# carrier_breakout_box_make-before-break.net
KiCad netlist of a schematic drawn in EAGLE
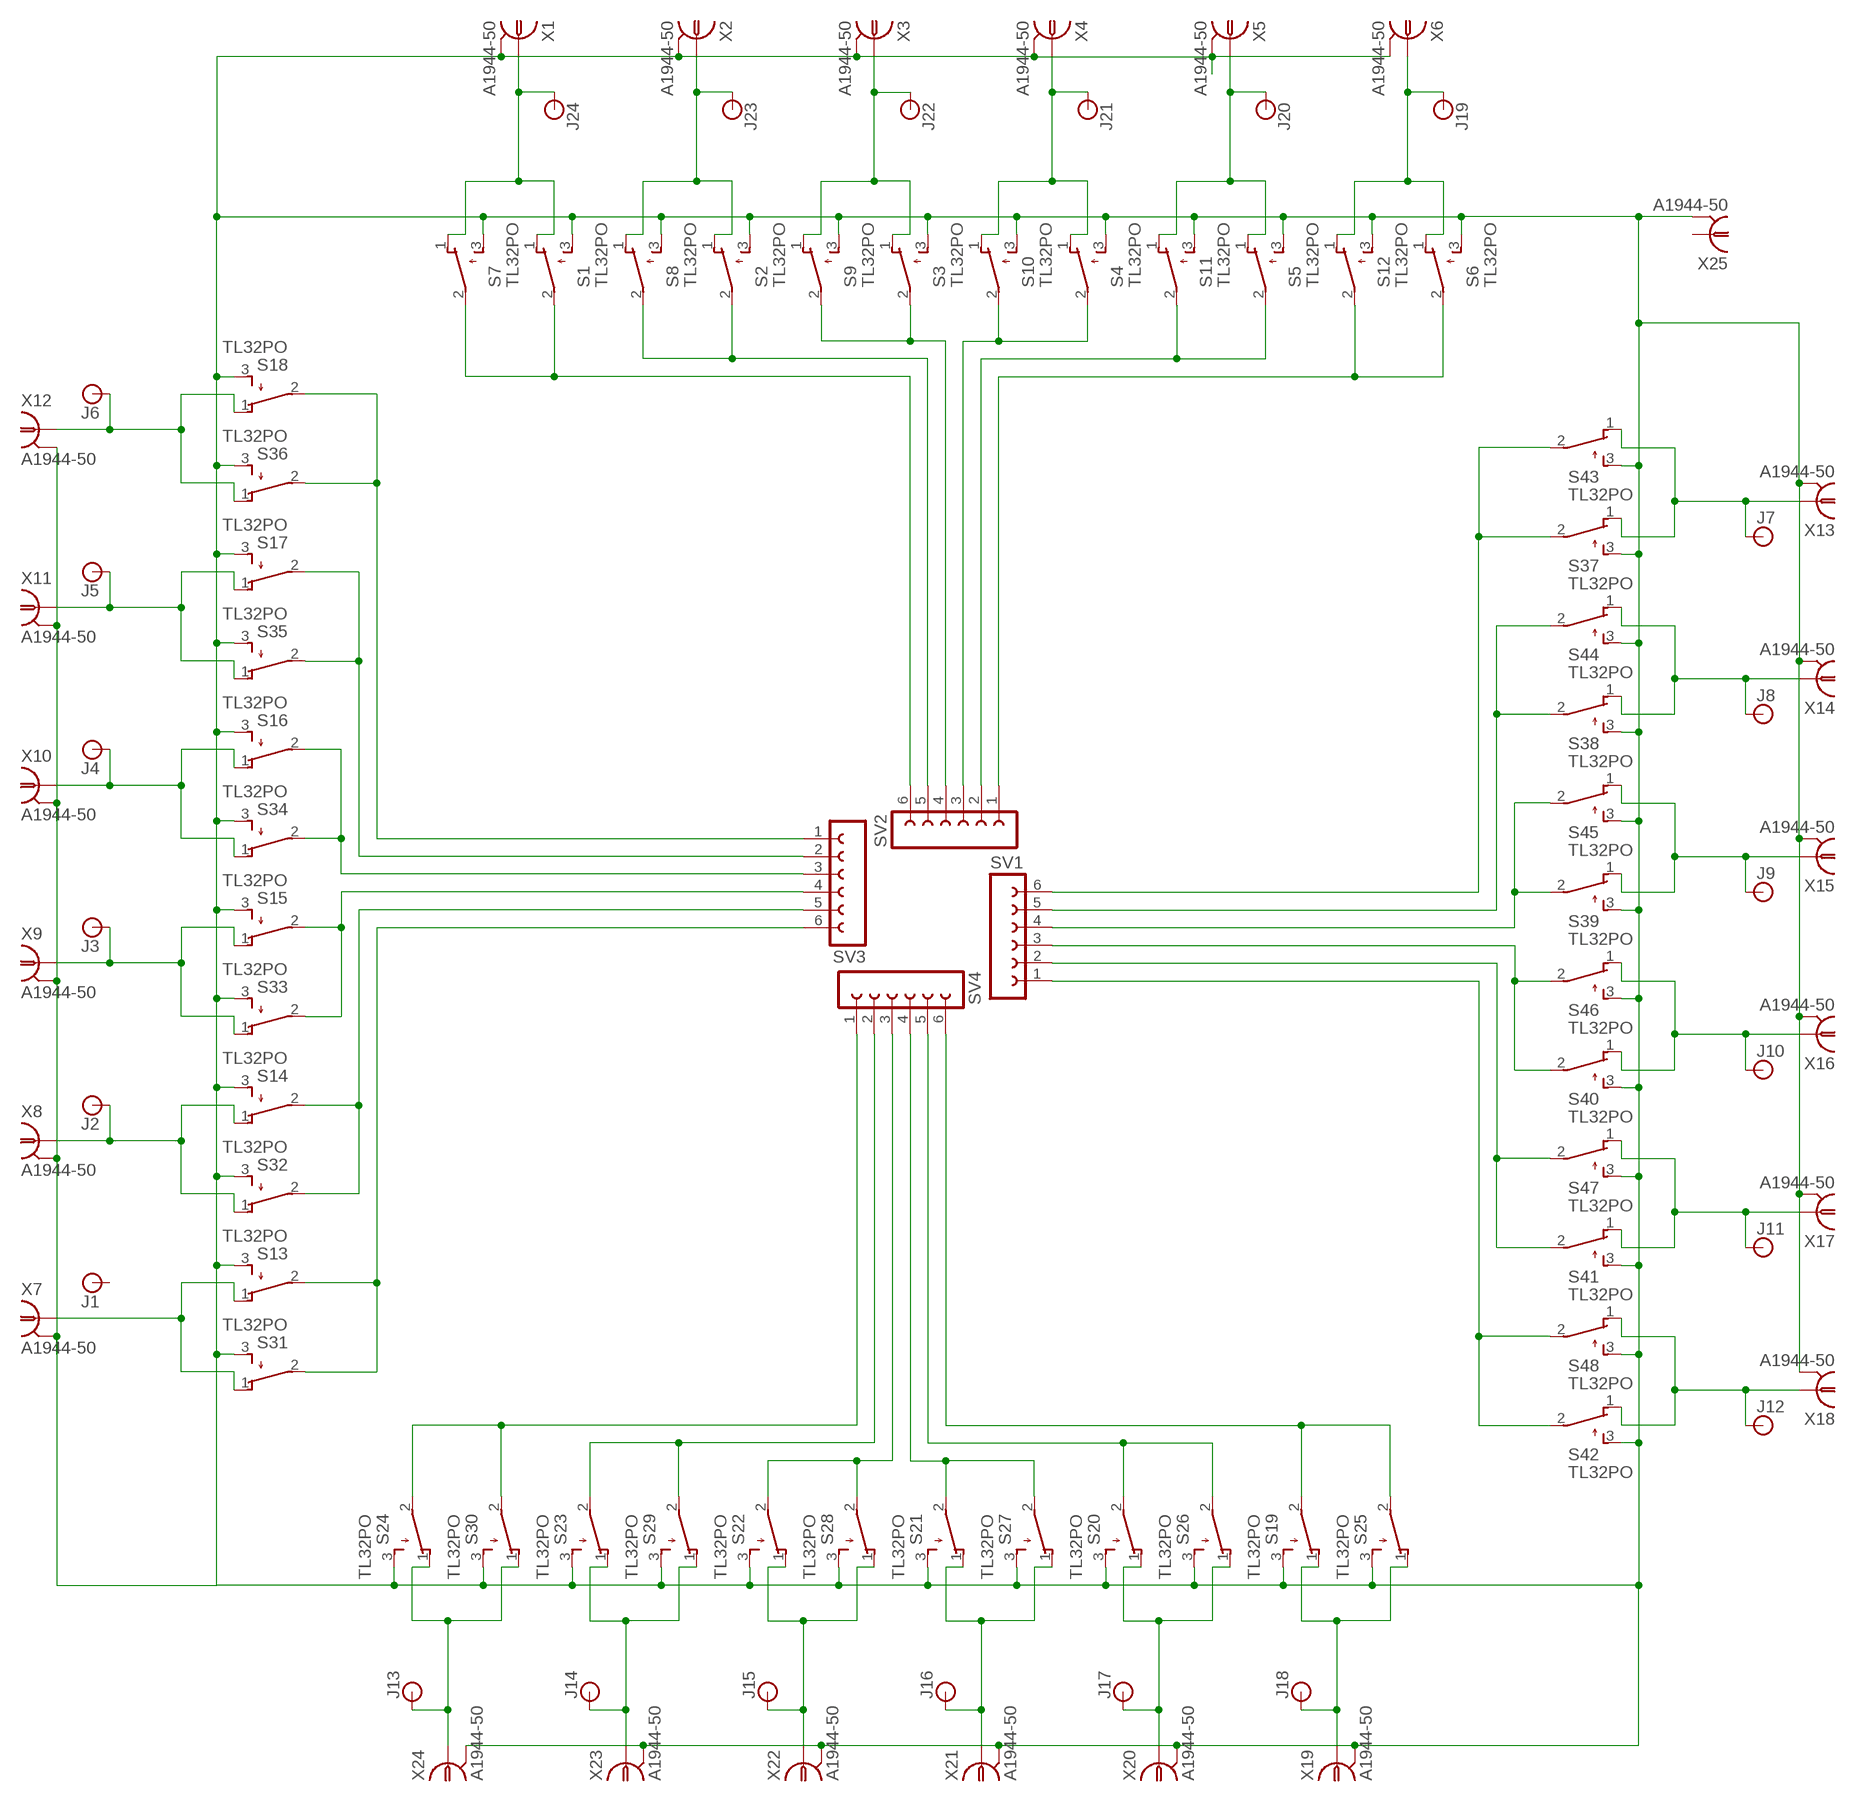
[diagram p0: schematic, sheet 1]

(export (version "E")
  (design (tool "Eeschema 10.0.6"))
  (components
    (comp (ref "J1")
      (value "BANANA_CONN")
      (footprint "eagle-import:BANANA_CONN")
      (libsource (lib "eagle-import") (part "BANANA_CONN"))
    )
    (comp (ref "J2")
      (value "BANANA_CONN")
      (footprint "eagle-import:BANANA_CONN")
      (libsource (lib "eagle-import") (part "BANANA_CONN"))
    )
    (comp (ref "J3")
      (value "BANANA_CONN")
      (footprint "eagle-import:BANANA_CONN")
      (libsource (lib "eagle-import") (part "BANANA_CONN"))
    )
    (comp (ref "J4")
      (value "BANANA_CONN")
      (footprint "eagle-import:BANANA_CONN")
      (libsource (lib "eagle-import") (part "BANANA_CONN"))
    )
    (comp (ref "J5")
      (value "BANANA_CONN")
      (footprint "eagle-import:BANANA_CONN")
      (libsource (lib "eagle-import") (part "BANANA_CONN"))
    )
    (comp (ref "J6")
      (value "BANANA_CONN")
      (footprint "eagle-import:BANANA_CONN")
      (libsource (lib "eagle-import") (part "BANANA_CONN"))
    )
    (comp (ref "J7")
      (value "BANANA_CONN")
      (footprint "eagle-import:BANANA_CONN")
      (libsource (lib "eagle-import") (part "BANANA_CONN"))
    )
    (comp (ref "J8")
      (value "BANANA_CONN")
      (footprint "eagle-import:BANANA_CONN")
      (libsource (lib "eagle-import") (part "BANANA_CONN"))
    )
    (comp (ref "J9")
      (value "BANANA_CONN")
      (footprint "eagle-import:BANANA_CONN")
      (libsource (lib "eagle-import") (part "BANANA_CONN"))
    )
    (comp (ref "J10")
      (value "BANANA_CONN")
      (footprint "eagle-import:BANANA_CONN")
      (libsource (lib "eagle-import") (part "BANANA_CONN"))
    )
    (comp (ref "J11")
      (value "BANANA_CONN")
      (footprint "eagle-import:BANANA_CONN")
      (libsource (lib "eagle-import") (part "BANANA_CONN"))
    )
    (comp (ref "J12")
      (value "BANANA_CONN")
      (footprint "eagle-import:BANANA_CONN")
      (libsource (lib "eagle-import") (part "BANANA_CONN"))
    )
    (comp (ref "J13")
      (value "BANANA_CONN")
      (footprint "eagle-import:BANANA_CONN")
      (libsource (lib "eagle-import") (part "BANANA_CONN"))
    )
    (comp (ref "J14")
      (value "BANANA_CONN")
      (footprint "eagle-import:BANANA_CONN")
      (libsource (lib "eagle-import") (part "BANANA_CONN"))
    )
    (comp (ref "J15")
      (value "BANANA_CONN")
      (footprint "eagle-import:BANANA_CONN")
      (libsource (lib "eagle-import") (part "BANANA_CONN"))
    )
    (comp (ref "J16")
      (value "BANANA_CONN")
      (footprint "eagle-import:BANANA_CONN")
      (libsource (lib "eagle-import") (part "BANANA_CONN"))
    )
    (comp (ref "J17")
      (value "BANANA_CONN")
      (footprint "eagle-import:BANANA_CONN")
      (libsource (lib "eagle-import") (part "BANANA_CONN"))
    )
    (comp (ref "J18")
      (value "BANANA_CONN")
      (footprint "eagle-import:BANANA_CONN")
      (libsource (lib "eagle-import") (part "BANANA_CONN"))
    )
    (comp (ref "J19")
      (value "BANANA_CONN")
      (footprint "eagle-import:BANANA_CONN")
      (libsource (lib "eagle-import") (part "BANANA_CONN"))
    )
    (comp (ref "J20")
      (value "BANANA_CONN")
      (footprint "eagle-import:BANANA_CONN")
      (libsource (lib "eagle-import") (part "BANANA_CONN"))
    )
    (comp (ref "J21")
      (value "BANANA_CONN")
      (footprint "eagle-import:BANANA_CONN")
      (libsource (lib "eagle-import") (part "BANANA_CONN"))
    )
    (comp (ref "J22")
      (value "BANANA_CONN")
      (footprint "eagle-import:BANANA_CONN")
      (libsource (lib "eagle-import") (part "BANANA_CONN"))
    )
    (comp (ref "J23")
      (value "BANANA_CONN")
      (footprint "eagle-import:BANANA_CONN")
      (libsource (lib "eagle-import") (part "BANANA_CONN"))
    )
    (comp (ref "J24")
      (value "BANANA_CONN")
      (footprint "eagle-import:BANANA_CONN")
      (libsource (lib "eagle-import") (part "BANANA_CONN"))
    )
    (comp (ref "S1")
      (value "TL32PO")
      (footprint "eagle-import:TL3XPO")
      (libsource (lib "eagle-import") (part "TL32PO"))
    )
    (comp (ref "S2")
      (value "TL32PO")
      (footprint "eagle-import:TL3XPO")
      (libsource (lib "eagle-import") (part "TL32PO"))
    )
    (comp (ref "S3")
      (value "TL32PO")
      (footprint "eagle-import:TL3XPO")
      (libsource (lib "eagle-import") (part "TL32PO"))
    )
    (comp (ref "S4")
      (value "TL32PO")
      (footprint "eagle-import:TL3XPO")
      (libsource (lib "eagle-import") (part "TL32PO"))
    )
    (comp (ref "S5")
      (value "TL32PO")
      (footprint "eagle-import:TL3XPO")
      (libsource (lib "eagle-import") (part "TL32PO"))
    )
    (comp (ref "S6")
      (value "TL32PO")
      (footprint "eagle-import:TL3XPO")
      (libsource (lib "eagle-import") (part "TL32PO"))
    )
    (comp (ref "S7")
      (value "TL32PO")
      (footprint "eagle-import:TL3XPO")
      (libsource (lib "eagle-import") (part "TL32PO"))
    )
    (comp (ref "S8")
      (value "TL32PO")
      (footprint "eagle-import:TL3XPO")
      (libsource (lib "eagle-import") (part "TL32PO"))
    )
    (comp (ref "S9")
      (value "TL32PO")
      (footprint "eagle-import:TL3XPO")
      (libsource (lib "eagle-import") (part "TL32PO"))
    )
    (comp (ref "S10")
      (value "TL32PO")
      (footprint "eagle-import:TL3XPO")
      (libsource (lib "eagle-import") (part "TL32PO"))
    )
    (comp (ref "S11")
      (value "TL32PO")
      (footprint "eagle-import:TL3XPO")
      (libsource (lib "eagle-import") (part "TL32PO"))
    )
    (comp (ref "S12")
      (value "TL32PO")
      (footprint "eagle-import:TL3XPO")
      (libsource (lib "eagle-import") (part "TL32PO"))
    )
    (comp (ref "S13")
      (value "TL32PO")
      (footprint "eagle-import:TL3XPO")
      (libsource (lib "eagle-import") (part "TL32PO"))
    )
    (comp (ref "S14")
      (value "TL32PO")
      (footprint "eagle-import:TL3XPO")
      (libsource (lib "eagle-import") (part "TL32PO"))
    )
    (comp (ref "S15")
      (value "TL32PO")
      (footprint "eagle-import:TL3XPO")
      (libsource (lib "eagle-import") (part "TL32PO"))
    )
    (comp (ref "S16")
      (value "TL32PO")
      (footprint "eagle-import:TL3XPO")
      (libsource (lib "eagle-import") (part "TL32PO"))
    )
    (comp (ref "S17")
      (value "TL32PO")
      (footprint "eagle-import:TL3XPO")
      (libsource (lib "eagle-import") (part "TL32PO"))
    )
    (comp (ref "S18")
      (value "TL32PO")
      (footprint "eagle-import:TL3XPO")
      (libsource (lib "eagle-import") (part "TL32PO"))
    )
    (comp (ref "S19")
      (value "TL32PO")
      (footprint "eagle-import:TL3XPO")
      (libsource (lib "eagle-import") (part "TL32PO"))
    )
    (comp (ref "S20")
      (value "TL32PO")
      (footprint "eagle-import:TL3XPO")
      (libsource (lib "eagle-import") (part "TL32PO"))
    )
    (comp (ref "S21")
      (value "TL32PO")
      (footprint "eagle-import:TL3XPO")
      (libsource (lib "eagle-import") (part "TL32PO"))
    )
    (comp (ref "S22")
      (value "TL32PO")
      (footprint "eagle-import:TL3XPO")
      (libsource (lib "eagle-import") (part "TL32PO"))
    )
    (comp (ref "S23")
      (value "TL32PO")
      (footprint "eagle-import:TL3XPO")
      (libsource (lib "eagle-import") (part "TL32PO"))
    )
    (comp (ref "S24")
      (value "TL32PO")
      (footprint "eagle-import:TL3XPO")
      (libsource (lib "eagle-import") (part "TL32PO"))
    )
    (comp (ref "S25")
      (value "TL32PO")
      (footprint "eagle-import:TL3XPO")
      (libsource (lib "eagle-import") (part "TL32PO"))
    )
    (comp (ref "S26")
      (value "TL32PO")
      (footprint "eagle-import:TL3XPO")
      (libsource (lib "eagle-import") (part "TL32PO"))
    )
    (comp (ref "S27")
      (value "TL32PO")
      (footprint "eagle-import:TL3XPO")
      (libsource (lib "eagle-import") (part "TL32PO"))
    )
    (comp (ref "S28")
      (value "TL32PO")
      (footprint "eagle-import:TL3XPO")
      (libsource (lib "eagle-import") (part "TL32PO"))
    )
    (comp (ref "S29")
      (value "TL32PO")
      (footprint "eagle-import:TL3XPO")
      (libsource (lib "eagle-import") (part "TL32PO"))
    )
    (comp (ref "S30")
      (value "TL32PO")
      (footprint "eagle-import:TL3XPO")
      (libsource (lib "eagle-import") (part "TL32PO"))
    )
    (comp (ref "S31")
      (value "TL32PO")
      (footprint "eagle-import:TL3XPO")
      (libsource (lib "eagle-import") (part "TL32PO"))
    )
    (comp (ref "S32")
      (value "TL32PO")
      (footprint "eagle-import:TL3XPO")
      (libsource (lib "eagle-import") (part "TL32PO"))
    )
    (comp (ref "S33")
      (value "TL32PO")
      (footprint "eagle-import:TL3XPO")
      (libsource (lib "eagle-import") (part "TL32PO"))
    )
    (comp (ref "S34")
      (value "TL32PO")
      (footprint "eagle-import:TL3XPO")
      (libsource (lib "eagle-import") (part "TL32PO"))
    )
    (comp (ref "S35")
      (value "TL32PO")
      (footprint "eagle-import:TL3XPO")
      (libsource (lib "eagle-import") (part "TL32PO"))
    )
    (comp (ref "S36")
      (value "TL32PO")
      (footprint "eagle-import:TL3XPO")
      (libsource (lib "eagle-import") (part "TL32PO"))
    )
    (comp (ref "S37")
      (value "TL32PO")
      (footprint "eagle-import:TL3XPO")
      (libsource (lib "eagle-import") (part "TL32PO"))
    )
    (comp (ref "S38")
      (value "TL32PO")
      (footprint "eagle-import:TL3XPO")
      (libsource (lib "eagle-import") (part "TL32PO"))
    )
    (comp (ref "S39")
      (value "TL32PO")
      (footprint "eagle-import:TL3XPO")
      (libsource (lib "eagle-import") (part "TL32PO"))
    )
    (comp (ref "S40")
      (value "TL32PO")
      (footprint "eagle-import:TL3XPO")
      (libsource (lib "eagle-import") (part "TL32PO"))
    )
    (comp (ref "S41")
      (value "TL32PO")
      (footprint "eagle-import:TL3XPO")
      (libsource (lib "eagle-import") (part "TL32PO"))
    )
    (comp (ref "S42")
      (value "TL32PO")
      (footprint "eagle-import:TL3XPO")
      (libsource (lib "eagle-import") (part "TL32PO"))
    )
    (comp (ref "S43")
      (value "TL32PO")
      (footprint "eagle-import:TL3XPO")
      (libsource (lib "eagle-import") (part "TL32PO"))
    )
    (comp (ref "S44")
      (value "TL32PO")
      (footprint "eagle-import:TL3XPO")
      (libsource (lib "eagle-import") (part "TL32PO"))
    )
    (comp (ref "S45")
      (value "TL32PO")
      (footprint "eagle-import:TL3XPO")
      (libsource (lib "eagle-import") (part "TL32PO"))
    )
    (comp (ref "S46")
      (value "TL32PO")
      (footprint "eagle-import:TL3XPO")
      (libsource (lib "eagle-import") (part "TL32PO"))
    )
    (comp (ref "S47")
      (value "TL32PO")
      (footprint "eagle-import:TL3XPO")
      (libsource (lib "eagle-import") (part "TL32PO"))
    )
    (comp (ref "S48")
      (value "TL32PO")
      (footprint "eagle-import:TL3XPO")
      (libsource (lib "eagle-import") (part "TL32PO"))
    )
    (comp (ref "SV1")
      (value "FE06-1")
      (footprint "eagle-import:FE06")
      (libsource (lib "eagle-import") (part "FE06-1"))
    )
    (comp (ref "SV2")
      (value "FE06-1")
      (footprint "eagle-import:FE06")
      (libsource (lib "eagle-import") (part "FE06-1"))
    )
    (comp (ref "SV3")
      (value "FE06-1")
      (footprint "eagle-import:FE06")
      (libsource (lib "eagle-import") (part "FE06-1"))
    )
    (comp (ref "SV4")
      (value "FE06-1")
      (footprint "eagle-import:FE06")
      (libsource (lib "eagle-import") (part "FE06-1"))
    )
    (comp (ref "X1")
      (value "A1944-50")
      (footprint "eagle-import:A1944")
      (libsource (lib "eagle-import") (part "A1944-50"))
    )
    (comp (ref "X2")
      (value "A1944-50")
      (footprint "eagle-import:A1944")
      (libsource (lib "eagle-import") (part "A1944-50"))
    )
    (comp (ref "X3")
      (value "A1944-50")
      (footprint "eagle-import:A1944")
      (libsource (lib "eagle-import") (part "A1944-50"))
    )
    (comp (ref "X4")
      (value "A1944-50")
      (footprint "eagle-import:A1944")
      (libsource (lib "eagle-import") (part "A1944-50"))
    )
    (comp (ref "X5")
      (value "A1944-50")
      (footprint "eagle-import:A1944")
      (libsource (lib "eagle-import") (part "A1944-50"))
    )
    (comp (ref "X6")
      (value "A1944-50")
      (footprint "eagle-import:A1944")
      (libsource (lib "eagle-import") (part "A1944-50"))
    )
    (comp (ref "X7")
      (value "A1944-50")
      (footprint "eagle-import:A1944")
      (libsource (lib "eagle-import") (part "A1944-50"))
    )
    (comp (ref "X8")
      (value "A1944-50")
      (footprint "eagle-import:A1944")
      (libsource (lib "eagle-import") (part "A1944-50"))
    )
    (comp (ref "X9")
      (value "A1944-50")
      (footprint "eagle-import:A1944")
      (libsource (lib "eagle-import") (part "A1944-50"))
    )
    (comp (ref "X10")
      (value "A1944-50")
      (footprint "eagle-import:A1944")
      (libsource (lib "eagle-import") (part "A1944-50"))
    )
    (comp (ref "X11")
      (value "A1944-50")
      (footprint "eagle-import:A1944")
      (libsource (lib "eagle-import") (part "A1944-50"))
    )
    (comp (ref "X12")
      (value "A1944-50")
      (footprint "eagle-import:A1944")
      (libsource (lib "eagle-import") (part "A1944-50"))
    )
    (comp (ref "X13")
      (value "A1944-50")
      (footprint "eagle-import:A1944")
      (libsource (lib "eagle-import") (part "A1944-50"))
    )
    (comp (ref "X14")
      (value "A1944-50")
      (footprint "eagle-import:A1944")
      (libsource (lib "eagle-import") (part "A1944-50"))
    )
    (comp (ref "X15")
      (value "A1944-50")
      (footprint "eagle-import:A1944")
      (libsource (lib "eagle-import") (part "A1944-50"))
    )
    (comp (ref "X16")
      (value "A1944-50")
      (footprint "eagle-import:A1944")
      (libsource (lib "eagle-import") (part "A1944-50"))
    )
    (comp (ref "X17")
      (value "A1944-50")
      (footprint "eagle-import:A1944")
      (libsource (lib "eagle-import") (part "A1944-50"))
    )
    (comp (ref "X18")
      (value "A1944-50")
      (footprint "eagle-import:A1944")
      (libsource (lib "eagle-import") (part "A1944-50"))
    )
    (comp (ref "X19")
      (value "A1944-50")
      (footprint "eagle-import:A1944")
      (libsource (lib "eagle-import") (part "A1944-50"))
    )
    (comp (ref "X20")
      (value "A1944-50")
      (footprint "eagle-import:A1944")
      (libsource (lib "eagle-import") (part "A1944-50"))
    )
    (comp (ref "X21")
      (value "A1944-50")
      (footprint "eagle-import:A1944")
      (libsource (lib "eagle-import") (part "A1944-50"))
    )
    (comp (ref "X22")
      (value "A1944-50")
      (footprint "eagle-import:A1944")
      (libsource (lib "eagle-import") (part "A1944-50"))
    )
    (comp (ref "X23")
      (value "A1944-50")
      (footprint "eagle-import:A1944")
      (libsource (lib "eagle-import") (part "A1944-50"))
    )
    (comp (ref "X24")
      (value "A1944-50")
      (footprint "eagle-import:A1944")
      (libsource (lib "eagle-import") (part "A1944-50"))
    )
    (comp (ref "X25")
      (value "A1944-50")
      (footprint "eagle-import:A1944")
      (libsource (lib "eagle-import") (part "A1944-50"))
    )
  )
  (nets
    (net (code "1") (name "Net-(J2-1)") (class "Default")
      (node (ref "J2") (pin "P$1") (pinfunction "1_P$1") (pintype "passive"))
      (node (ref "S14") (pin "1") (pinfunction "O_1") (pintype "passive"))
      (node (ref "S32") (pin "1") (pinfunction "O_1") (pintype "passive"))
      (node (ref "X8") (pin "1") (pinfunction "1_1") (pintype "passive"))
    )
    (net (code "2") (name "Net-(J3-1)") (class "Default")
      (node (ref "J3") (pin "P$1") (pinfunction "1_P$1") (pintype "passive"))
      (node (ref "S15") (pin "1") (pinfunction "O_1") (pintype "passive"))
      (node (ref "S33") (pin "1") (pinfunction "O_1") (pintype "passive"))
      (node (ref "X9") (pin "1") (pinfunction "1_1") (pintype "passive"))
    )
    (net (code "3") (name "Net-(J4-1)") (class "Default")
      (node (ref "J4") (pin "P$1") (pinfunction "1_P$1") (pintype "passive"))
      (node (ref "S16") (pin "1") (pinfunction "O_1") (pintype "passive"))
      (node (ref "S34") (pin "1") (pinfunction "O_1") (pintype "passive"))
      (node (ref "X10") (pin "1") (pinfunction "1_1") (pintype "passive"))
    )
    (net (code "4") (name "Net-(J5-1)") (class "Default")
      (node (ref "J5") (pin "P$1") (pinfunction "1_P$1") (pintype "passive"))
      (node (ref "S17") (pin "1") (pinfunction "O_1") (pintype "passive"))
      (node (ref "S35") (pin "1") (pinfunction "O_1") (pintype "passive"))
      (node (ref "X11") (pin "1") (pinfunction "1_1") (pintype "passive"))
    )
    (net (code "5") (name "Net-(J6-1)") (class "Default")
      (node (ref "J6") (pin "P$1") (pinfunction "1_P$1") (pintype "passive"))
      (node (ref "S18") (pin "1") (pinfunction "O_1") (pintype "passive"))
      (node (ref "S36") (pin "1") (pinfunction "O_1") (pintype "passive"))
      (node (ref "X12") (pin "1") (pinfunction "1_1") (pintype "passive"))
    )
    (net (code "6") (name "Net-(J7-1)") (class "Default")
      (node (ref "J7") (pin "P$1") (pinfunction "1_P$1") (pintype "passive"))
      (node (ref "S37") (pin "1") (pinfunction "O_1") (pintype "passive"))
      (node (ref "S43") (pin "1") (pinfunction "O_1") (pintype "passive"))
      (node (ref "X13") (pin "1") (pinfunction "1_1") (pintype "passive"))
    )
    (net (code "7") (name "Net-(J8-1)") (class "Default")
      (node (ref "J8") (pin "P$1") (pinfunction "1_P$1") (pintype "passive"))
      (node (ref "S38") (pin "1") (pinfunction "O_1") (pintype "passive"))
      (node (ref "S44") (pin "1") (pinfunction "O_1") (pintype "passive"))
      (node (ref "X14") (pin "1") (pinfunction "1_1") (pintype "passive"))
    )
    (net (code "8") (name "Net-(J9-1)") (class "Default")
      (node (ref "J9") (pin "P$1") (pinfunction "1_P$1") (pintype "passive"))
      (node (ref "S39") (pin "1") (pinfunction "O_1") (pintype "passive"))
      (node (ref "S45") (pin "1") (pinfunction "O_1") (pintype "passive"))
      (node (ref "X15") (pin "1") (pinfunction "1_1") (pintype "passive"))
    )
    (net (code "9") (name "Net-(J10-1)") (class "Default")
      (node (ref "J10") (pin "P$1") (pinfunction "1_P$1") (pintype "passive"))
      (node (ref "S40") (pin "1") (pinfunction "O_1") (pintype "passive"))
      (node (ref "S46") (pin "1") (pinfunction "O_1") (pintype "passive"))
      (node (ref "X16") (pin "1") (pinfunction "1_1") (pintype "passive"))
    )
    (net (code "10") (name "Net-(J11-1)") (class "Default")
      (node (ref "J11") (pin "P$1") (pinfunction "1_P$1") (pintype "passive"))
      (node (ref "S41") (pin "1") (pinfunction "O_1") (pintype "passive"))
      (node (ref "S47") (pin "1") (pinfunction "O_1") (pintype "passive"))
      (node (ref "X17") (pin "1") (pinfunction "1_1") (pintype "passive"))
    )
    (net (code "11") (name "Net-(J12-1)") (class "Default")
      (node (ref "J12") (pin "P$1") (pinfunction "1_P$1") (pintype "passive"))
      (node (ref "S42") (pin "1") (pinfunction "O_1") (pintype "passive"))
      (node (ref "S48") (pin "1") (pinfunction "O_1") (pintype "passive"))
      (node (ref "X18") (pin "1") (pinfunction "1_1") (pintype "passive"))
    )
    (net (code "12") (name "Net-(J13-1)") (class "Default")
      (node (ref "J13") (pin "P$1") (pinfunction "1_P$1") (pintype "passive"))
      (node (ref "S24") (pin "1") (pinfunction "O_1") (pintype "passive"))
      (node (ref "S30") (pin "1") (pinfunction "O_1") (pintype "passive"))
      (node (ref "X24") (pin "1") (pinfunction "1_1") (pintype "passive"))
    )
    (net (code "13") (name "Net-(J14-1)") (class "Default")
      (node (ref "J14") (pin "P$1") (pinfunction "1_P$1") (pintype "passive"))
      (node (ref "S23") (pin "1") (pinfunction "O_1") (pintype "passive"))
      (node (ref "S29") (pin "1") (pinfunction "O_1") (pintype "passive"))
      (node (ref "X23") (pin "1") (pinfunction "1_1") (pintype "passive"))
    )
    (net (code "14") (name "Net-(J15-1)") (class "Default")
      (node (ref "J15") (pin "P$1") (pinfunction "1_P$1") (pintype "passive"))
      (node (ref "S22") (pin "1") (pinfunction "O_1") (pintype "passive"))
      (node (ref "S28") (pin "1") (pinfunction "O_1") (pintype "passive"))
      (node (ref "X22") (pin "1") (pinfunction "1_1") (pintype "passive"))
    )
    (net (code "15") (name "Net-(J16-1)") (class "Default")
      (node (ref "J16") (pin "P$1") (pinfunction "1_P$1") (pintype "passive"))
      (node (ref "S21") (pin "1") (pinfunction "O_1") (pintype "passive"))
      (node (ref "S27") (pin "1") (pinfunction "O_1") (pintype "passive"))
      (node (ref "X21") (pin "1") (pinfunction "1_1") (pintype "passive"))
    )
    (net (code "16") (name "Net-(J17-1)") (class "Default")
      (node (ref "J17") (pin "P$1") (pinfunction "1_P$1") (pintype "passive"))
      (node (ref "S20") (pin "1") (pinfunction "O_1") (pintype "passive"))
      (node (ref "S26") (pin "1") (pinfunction "O_1") (pintype "passive"))
      (node (ref "X20") (pin "1") (pinfunction "1_1") (pintype "passive"))
    )
    (net (code "17") (name "Net-(J18-1)") (class "Default")
      (node (ref "J18") (pin "P$1") (pinfunction "1_P$1") (pintype "passive"))
      (node (ref "S19") (pin "1") (pinfunction "O_1") (pintype "passive"))
      (node (ref "S25") (pin "1") (pinfunction "O_1") (pintype "passive"))
      (node (ref "X19") (pin "1") (pinfunction "1_1") (pintype "passive"))
    )
    (net (code "18") (name "Net-(J19-1)") (class "Default")
      (node (ref "J19") (pin "P$1") (pinfunction "1_P$1") (pintype "passive"))
      (node (ref "S12") (pin "1") (pinfunction "O_1") (pintype "passive"))
      (node (ref "S6") (pin "1") (pinfunction "O_1") (pintype "passive"))
      (node (ref "X6") (pin "1") (pinfunction "1_1") (pintype "passive"))
    )
    (net (code "19") (name "Net-(J20-1)") (class "Default")
      (node (ref "J20") (pin "P$1") (pinfunction "1_P$1") (pintype "passive"))
      (node (ref "S11") (pin "1") (pinfunction "O_1") (pintype "passive"))
      (node (ref "S5") (pin "1") (pinfunction "O_1") (pintype "passive"))
      (node (ref "X5") (pin "1") (pinfunction "1_1") (pintype "passive"))
    )
    (net (code "20") (name "Net-(J21-1)") (class "Default")
      (node (ref "J21") (pin "P$1") (pinfunction "1_P$1") (pintype "passive"))
      (node (ref "S10") (pin "1") (pinfunction "O_1") (pintype "passive"))
      (node (ref "S4") (pin "1") (pinfunction "O_1") (pintype "passive"))
      (node (ref "X4") (pin "1") (pinfunction "1_1") (pintype "passive"))
    )
    (net (code "21") (name "Net-(J22-1)") (class "Default")
      (node (ref "J22") (pin "P$1") (pinfunction "1_P$1") (pintype "passive"))
      (node (ref "S3") (pin "1") (pinfunction "O_1") (pintype "passive"))
      (node (ref "S9") (pin "1") (pinfunction "O_1") (pintype "passive"))
      (node (ref "X3") (pin "1") (pinfunction "1_1") (pintype "passive"))
    )
    (net (code "22") (name "Net-(J23-1)") (class "Default")
      (node (ref "J23") (pin "P$1") (pinfunction "1_P$1") (pintype "passive"))
      (node (ref "S2") (pin "1") (pinfunction "O_1") (pintype "passive"))
      (node (ref "S8") (pin "1") (pinfunction "O_1") (pintype "passive"))
      (node (ref "X2") (pin "1") (pinfunction "1_1") (pintype "passive"))
    )
    (net (code "23") (name "Net-(J24-1)") (class "Default")
      (node (ref "J24") (pin "P$1") (pinfunction "1_P$1") (pintype "passive"))
      (node (ref "S1") (pin "1") (pinfunction "O_1") (pintype "passive"))
      (node (ref "S7") (pin "1") (pinfunction "O_1") (pintype "passive"))
      (node (ref "X1") (pin "1") (pinfunction "1_1") (pintype "passive"))
    )
    (net (code "24") (name "Net-(S1-P)") (class "Default")
      (node (ref "S1") (pin "2") (pinfunction "P_2") (pintype "passive"))
      (node (ref "S7") (pin "2") (pinfunction "P_2") (pintype "passive"))
      (node (ref "SV2") (pin "6") (pinfunction "6_6") (pintype "passive"))
    )
    (net (code "25") (name "Net-(S1-S)") (class "Default")
      (node (ref "S1") (pin "3") (pinfunction "S_3") (pintype "passive"))
      (node (ref "S10") (pin "3") (pinfunction "S_3") (pintype "passive"))
      (node (ref "S11") (pin "3") (pinfunction "S_3") (pintype "passive"))
      (node (ref "S12") (pin "3") (pinfunction "S_3") (pintype "passive"))
      (node (ref "S13") (pin "3") (pinfunction "S_3") (pintype "passive"))
      (node (ref "S14") (pin "3") (pinfunction "S_3") (pintype "passive"))
      (node (ref "S15") (pin "3") (pinfunction "S_3") (pintype "passive"))
      (node (ref "S16") (pin "3") (pinfunction "S_3") (pintype "passive"))
      (node (ref "S17") (pin "3") (pinfunction "S_3") (pintype "passive"))
      (node (ref "S18") (pin "3") (pinfunction "S_3") (pintype "passive"))
      (node (ref "S19") (pin "3") (pinfunction "S_3") (pintype "passive"))
      (node (ref "S2") (pin "3") (pinfunction "S_3") (pintype "passive"))
      (node (ref "S20") (pin "3") (pinfunction "S_3") (pintype "passive"))
      (node (ref "S21") (pin "3") (pinfunction "S_3") (pintype "passive"))
      (node (ref "S22") (pin "3") (pinfunction "S_3") (pintype "passive"))
      (node (ref "S23") (pin "3") (pinfunction "S_3") (pintype "passive"))
      (node (ref "S24") (pin "3") (pinfunction "S_3") (pintype "passive"))
      (node (ref "S25") (pin "3") (pinfunction "S_3") (pintype "passive"))
      (node (ref "S26") (pin "3") (pinfunction "S_3") (pintype "passive"))
      (node (ref "S27") (pin "3") (pinfunction "S_3") (pintype "passive"))
      (node (ref "S28") (pin "3") (pinfunction "S_3") (pintype "passive"))
      (node (ref "S29") (pin "3") (pinfunction "S_3") (pintype "passive"))
      (node (ref "S3") (pin "3") (pinfunction "S_3") (pintype "passive"))
      (node (ref "S30") (pin "3") (pinfunction "S_3") (pintype "passive"))
      (node (ref "S31") (pin "3") (pinfunction "S_3") (pintype "passive"))
      (node (ref "S32") (pin "3") (pinfunction "S_3") (pintype "passive"))
      (node (ref "S33") (pin "3") (pinfunction "S_3") (pintype "passive"))
      (node (ref "S34") (pin "3") (pinfunction "S_3") (pintype "passive"))
      (node (ref "S35") (pin "3") (pinfunction "S_3") (pintype "passive"))
      (node (ref "S36") (pin "3") (pinfunction "S_3") (pintype "passive"))
      (node (ref "S37") (pin "3") (pinfunction "S_3") (pintype "passive"))
      (node (ref "S38") (pin "3") (pinfunction "S_3") (pintype "passive"))
      (node (ref "S39") (pin "3") (pinfunction "S_3") (pintype "passive"))
      (node (ref "S4") (pin "3") (pinfunction "S_3") (pintype "passive"))
      (node (ref "S40") (pin "3") (pinfunction "S_3") (pintype "passive"))
      (node (ref "S41") (pin "3") (pinfunction "S_3") (pintype "passive"))
      (node (ref "S42") (pin "3") (pinfunction "S_3") (pintype "passive"))
      (node (ref "S43") (pin "3") (pinfunction "S_3") (pintype "passive"))
      (node (ref "S44") (pin "3") (pinfunction "S_3") (pintype "passive"))
      (node (ref "S45") (pin "3") (pinfunction "S_3") (pintype "passive"))
      (node (ref "S46") (pin "3") (pinfunction "S_3") (pintype "passive"))
      (node (ref "S47") (pin "3") (pinfunction "S_3") (pintype "passive"))
      (node (ref "S48") (pin "3") (pinfunction "S_3") (pintype "passive"))
      (node (ref "S5") (pin "3") (pinfunction "S_3") (pintype "passive"))
      (node (ref "S6") (pin "3") (pinfunction "S_3") (pintype "passive"))
      (node (ref "S7") (pin "3") (pinfunction "S_3") (pintype "passive"))
      (node (ref "S8") (pin "3") (pinfunction "S_3") (pintype "passive"))
      (node (ref "S9") (pin "3") (pinfunction "S_3") (pintype "passive"))
      (node (ref "X1") (pin "2") (pinfunction "2_2") (pintype "passive"))
      (node (ref "X1") (pin "3") (pinfunction "2_3") (pintype "passive"))
      (node (ref "X1") (pin "4") (pinfunction "2_4") (pintype "passive"))
      (node (ref "X1") (pin "5") (pinfunction "2_5") (pintype "passive"))
      (node (ref "X10") (pin "2") (pinfunction "2_2") (pintype "passive"))
      (node (ref "X10") (pin "3") (pinfunction "2_3") (pintype "passive"))
      (node (ref "X10") (pin "4") (pinfunction "2_4") (pintype "passive"))
      (node (ref "X10") (pin "5") (pinfunction "2_5") (pintype "passive"))
      (node (ref "X11") (pin "2") (pinfunction "2_2") (pintype "passive"))
      (node (ref "X11") (pin "3") (pinfunction "2_3") (pintype "passive"))
      (node (ref "X11") (pin "4") (pinfunction "2_4") (pintype "passive"))
      (node (ref "X11") (pin "5") (pinfunction "2_5") (pintype "passive"))
      (node (ref "X12") (pin "2") (pinfunction "2_2") (pintype "passive"))
      (node (ref "X12") (pin "3") (pinfunction "2_3") (pintype "passive"))
      (node (ref "X12") (pin "4") (pinfunction "2_4") (pintype "passive"))
      (node (ref "X12") (pin "5") (pinfunction "2_5") (pintype "passive"))
      (node (ref "X13") (pin "2") (pinfunction "2_2") (pintype "passive"))
      (node (ref "X13") (pin "3") (pinfunction "2_3") (pintype "passive"))
      (node (ref "X13") (pin "4") (pinfunction "2_4") (pintype "passive"))
      (node (ref "X13") (pin "5") (pinfunction "2_5") (pintype "passive"))
      (node (ref "X14") (pin "2") (pinfunction "2_2") (pintype "passive"))
      (node (ref "X14") (pin "3") (pinfunction "2_3") (pintype "passive"))
      (node (ref "X14") (pin "4") (pinfunction "2_4") (pintype "passive"))
      (node (ref "X14") (pin "5") (pinfunction "2_5") (pintype "passive"))
      (node (ref "X15") (pin "2") (pinfunction "2_2") (pintype "passive"))
      (node (ref "X15") (pin "3") (pinfunction "2_3") (pintype "passive"))
      (node (ref "X15") (pin "4") (pinfunction "2_4") (pintype "passive"))
      (node (ref "X15") (pin "5") (pinfunction "2_5") (pintype "passive"))
      (node (ref "X16") (pin "2") (pinfunction "2_2") (pintype "passive"))
      (node (ref "X16") (pin "3") (pinfunction "2_3") (pintype "passive"))
      (node (ref "X16") (pin "4") (pinfunction "2_4") (pintype "passive"))
      (node (ref "X16") (pin "5") (pinfunction "2_5") (pintype "passive"))
      (node (ref "X17") (pin "2") (pinfunction "2_2") (pintype "passive"))
      (node (ref "X17") (pin "3") (pinfunction "2_3") (pintype "passive"))
      (node (ref "X17") (pin "4") (pinfunction "2_4") (pintype "passive"))
      (node (ref "X17") (pin "5") (pinfunction "2_5") (pintype "passive"))
      (node (ref "X18") (pin "2") (pinfunction "2_2") (pintype "passive"))
      (node (ref "X18") (pin "3") (pinfunction "2_3") (pintype "passive"))
      (node (ref "X18") (pin "4") (pinfunction "2_4") (pintype "passive"))
      (node (ref "X18") (pin "5") (pinfunction "2_5") (pintype "passive"))
      (node (ref "X19") (pin "2") (pinfunction "2_2") (pintype "passive"))
      (node (ref "X19") (pin "3") (pinfunction "2_3") (pintype "passive"))
      (node (ref "X19") (pin "4") (pinfunction "2_4") (pintype "passive"))
      (node (ref "X19") (pin "5") (pinfunction "2_5") (pintype "passive"))
      (node (ref "X2") (pin "2") (pinfunction "2_2") (pintype "passive"))
      (node (ref "X2") (pin "3") (pinfunction "2_3") (pintype "passive"))
      (node (ref "X2") (pin "4") (pinfunction "2_4") (pintype "passive"))
      (node (ref "X2") (pin "5") (pinfunction "2_5") (pintype "passive"))
      (node (ref "X20") (pin "2") (pinfunction "2_2") (pintype "passive"))
      (node (ref "X20") (pin "3") (pinfunction "2_3") (pintype "passive"))
      (node (ref "X20") (pin "4") (pinfunction "2_4") (pintype "passive"))
      (node (ref "X20") (pin "5") (pinfunction "2_5") (pintype "passive"))
      (node (ref "X21") (pin "2") (pinfunction "2_2") (pintype "passive"))
      (node (ref "X21") (pin "3") (pinfunction "2_3") (pintype "passive"))
      (node (ref "X21") (pin "4") (pinfunction "2_4") (pintype "passive"))
      (node (ref "X21") (pin "5") (pinfunction "2_5") (pintype "passive"))
      (node (ref "X22") (pin "2") (pinfunction "2_2") (pintype "passive"))
      (node (ref "X22") (pin "3") (pinfunction "2_3") (pintype "passive"))
      (node (ref "X22") (pin "4") (pinfunction "2_4") (pintype "passive"))
      (node (ref "X22") (pin "5") (pinfunction "2_5") (pintype "passive"))
      (node (ref "X23") (pin "2") (pinfunction "2_2") (pintype "passive"))
      (node (ref "X23") (pin "3") (pinfunction "2_3") (pintype "passive"))
      (node (ref "X23") (pin "4") (pinfunction "2_4") (pintype "passive"))
      (node (ref "X23") (pin "5") (pinfunction "2_5") (pintype "passive"))
      (node (ref "X24") (pin "2") (pinfunction "2_2") (pintype "passive"))
      (node (ref "X24") (pin "3") (pinfunction "2_3") (pintype "passive"))
      (node (ref "X24") (pin "4") (pinfunction "2_4") (pintype "passive"))
      (node (ref "X24") (pin "5") (pinfunction "2_5") (pintype "passive"))
      (node (ref "X25") (pin "2") (pinfunction "2_2") (pintype "passive"))
      (node (ref "X25") (pin "3") (pinfunction "2_3") (pintype "passive"))
      (node (ref "X25") (pin "4") (pinfunction "2_4") (pintype "passive"))
      (node (ref "X25") (pin "5") (pinfunction "2_5") (pintype "passive"))
      (node (ref "X3") (pin "2") (pinfunction "2_2") (pintype "passive"))
      (node (ref "X3") (pin "3") (pinfunction "2_3") (pintype "passive"))
      (node (ref "X3") (pin "4") (pinfunction "2_4") (pintype "passive"))
      (node (ref "X3") (pin "5") (pinfunction "2_5") (pintype "passive"))
      (node (ref "X4") (pin "2") (pinfunction "2_2") (pintype "passive"))
      (node (ref "X4") (pin "3") (pinfunction "2_3") (pintype "passive"))
      (node (ref "X4") (pin "4") (pinfunction "2_4") (pintype "passive"))
      (node (ref "X4") (pin "5") (pinfunction "2_5") (pintype "passive"))
      (node (ref "X5") (pin "2") (pinfunction "2_2") (pintype "passive"))
      (node (ref "X5") (pin "3") (pinfunction "2_3") (pintype "passive"))
      (node (ref "X5") (pin "4") (pinfunction "2_4") (pintype "passive"))
      (node (ref "X5") (pin "5") (pinfunction "2_5") (pintype "passive"))
      (node (ref "X6") (pin "2") (pinfunction "2_2") (pintype "passive"))
      (node (ref "X6") (pin "3") (pinfunction "2_3") (pintype "passive"))
      (node (ref "X6") (pin "4") (pinfunction "2_4") (pintype "passive"))
      (node (ref "X6") (pin "5") (pinfunction "2_5") (pintype "passive"))
      (node (ref "X7") (pin "2") (pinfunction "2_2") (pintype "passive"))
      (node (ref "X7") (pin "3") (pinfunction "2_3") (pintype "passive"))
      (node (ref "X7") (pin "4") (pinfunction "2_4") (pintype "passive"))
      (node (ref "X7") (pin "5") (pinfunction "2_5") (pintype "passive"))
      (node (ref "X8") (pin "2") (pinfunction "2_2") (pintype "passive"))
      (node (ref "X8") (pin "3") (pinfunction "2_3") (pintype "passive"))
      (node (ref "X8") (pin "4") (pinfunction "2_4") (pintype "passive"))
      (node (ref "X8") (pin "5") (pinfunction "2_5") (pintype "passive"))
      (node (ref "X9") (pin "2") (pinfunction "2_2") (pintype "passive"))
      (node (ref "X9") (pin "3") (pinfunction "2_3") (pintype "passive"))
      (node (ref "X9") (pin "4") (pinfunction "2_4") (pintype "passive"))
      (node (ref "X9") (pin "5") (pinfunction "2_5") (pintype "passive"))
    )
    (net (code "26") (name "Net-(S2-P)") (class "Default")
      (node (ref "S2") (pin "2") (pinfunction "P_2") (pintype "passive"))
      (node (ref "S8") (pin "2") (pinfunction "P_2") (pintype "passive"))
      (node (ref "SV2") (pin "5") (pinfunction "5_5") (pintype "passive"))
    )
    (net (code "27") (name "Net-(S3-P)") (class "Default")
      (node (ref "S3") (pin "2") (pinfunction "P_2") (pintype "passive"))
      (node (ref "S9") (pin "2") (pinfunction "P_2") (pintype "passive"))
      (node (ref "SV2") (pin "4") (pinfunction "4_4") (pintype "passive"))
    )
    (net (code "28") (name "Net-(S10-P)") (class "Default")
      (node (ref "S10") (pin "2") (pinfunction "P_2") (pintype "passive"))
      (node (ref "S4") (pin "2") (pinfunction "P_2") (pintype "passive"))
      (node (ref "SV2") (pin "3") (pinfunction "3_3") (pintype "passive"))
    )
    (net (code "29") (name "Net-(S11-P)") (class "Default")
      (node (ref "S11") (pin "2") (pinfunction "P_2") (pintype "passive"))
      (node (ref "S5") (pin "2") (pinfunction "P_2") (pintype "passive"))
      (node (ref "SV2") (pin "2") (pinfunction "2_2") (pintype "passive"))
    )
    (net (code "30") (name "Net-(S12-P)") (class "Default")
      (node (ref "S12") (pin "2") (pinfunction "P_2") (pintype "passive"))
      (node (ref "S6") (pin "2") (pinfunction "P_2") (pintype "passive"))
      (node (ref "SV2") (pin "1") (pinfunction "1_1") (pintype "passive"))
    )
    (net (code "31") (name "Net-(S13-O)") (class "Default")
      (node (ref "S13") (pin "1") (pinfunction "O_1") (pintype "passive"))
      (node (ref "S31") (pin "1") (pinfunction "O_1") (pintype "passive"))
      (node (ref "X7") (pin "1") (pinfunction "1_1") (pintype "passive"))
    )
    (net (code "32") (name "Net-(S13-P)") (class "Default")
      (node (ref "S13") (pin "2") (pinfunction "P_2") (pintype "passive"))
      (node (ref "S31") (pin "2") (pinfunction "P_2") (pintype "passive"))
      (node (ref "SV3") (pin "6") (pinfunction "6_6") (pintype "passive"))
    )
    (net (code "33") (name "Net-(S14-P)") (class "Default")
      (node (ref "S14") (pin "2") (pinfunction "P_2") (pintype "passive"))
      (node (ref "S32") (pin "2") (pinfunction "P_2") (pintype "passive"))
      (node (ref "SV3") (pin "5") (pinfunction "5_5") (pintype "passive"))
    )
    (net (code "34") (name "Net-(S15-P)") (class "Default")
      (node (ref "S15") (pin "2") (pinfunction "P_2") (pintype "passive"))
      (node (ref "S33") (pin "2") (pinfunction "P_2") (pintype "passive"))
      (node (ref "SV3") (pin "4") (pinfunction "4_4") (pintype "passive"))
    )
    (net (code "35") (name "Net-(S16-P)") (class "Default")
      (node (ref "S16") (pin "2") (pinfunction "P_2") (pintype "passive"))
      (node (ref "S34") (pin "2") (pinfunction "P_2") (pintype "passive"))
      (node (ref "SV3") (pin "3") (pinfunction "3_3") (pintype "passive"))
    )
    (net (code "36") (name "Net-(S17-P)") (class "Default")
      (node (ref "S17") (pin "2") (pinfunction "P_2") (pintype "passive"))
      (node (ref "S35") (pin "2") (pinfunction "P_2") (pintype "passive"))
      (node (ref "SV3") (pin "2") (pinfunction "2_2") (pintype "passive"))
    )
    (net (code "37") (name "Net-(S18-P)") (class "Default")
      (node (ref "S18") (pin "2") (pinfunction "P_2") (pintype "passive"))
      (node (ref "S36") (pin "2") (pinfunction "P_2") (pintype "passive"))
      (node (ref "SV3") (pin "1") (pinfunction "1_1") (pintype "passive"))
    )
    (net (code "38") (name "Net-(S19-P)") (class "Default")
      (node (ref "S19") (pin "2") (pinfunction "P_2") (pintype "passive"))
      (node (ref "S25") (pin "2") (pinfunction "P_2") (pintype "passive"))
      (node (ref "SV4") (pin "6") (pinfunction "6_6") (pintype "passive"))
    )
    (net (code "39") (name "Net-(S20-P)") (class "Default")
      (node (ref "S20") (pin "2") (pinfunction "P_2") (pintype "passive"))
      (node (ref "S26") (pin "2") (pinfunction "P_2") (pintype "passive"))
      (node (ref "SV4") (pin "5") (pinfunction "5_5") (pintype "passive"))
    )
    (net (code "40") (name "Net-(S21-P)") (class "Default")
      (node (ref "S21") (pin "2") (pinfunction "P_2") (pintype "passive"))
      (node (ref "S27") (pin "2") (pinfunction "P_2") (pintype "passive"))
      (node (ref "SV4") (pin "4") (pinfunction "4_4") (pintype "passive"))
    )
    (net (code "41") (name "Net-(S22-P)") (class "Default")
      (node (ref "S22") (pin "2") (pinfunction "P_2") (pintype "passive"))
      (node (ref "S28") (pin "2") (pinfunction "P_2") (pintype "passive"))
      (node (ref "SV4") (pin "3") (pinfunction "3_3") (pintype "passive"))
    )
    (net (code "42") (name "Net-(S23-P)") (class "Default")
      (node (ref "S23") (pin "2") (pinfunction "P_2") (pintype "passive"))
      (node (ref "S29") (pin "2") (pinfunction "P_2") (pintype "passive"))
      (node (ref "SV4") (pin "2") (pinfunction "2_2") (pintype "passive"))
    )
    (net (code "43") (name "Net-(S24-P)") (class "Default")
      (node (ref "S24") (pin "2") (pinfunction "P_2") (pintype "passive"))
      (node (ref "S30") (pin "2") (pinfunction "P_2") (pintype "passive"))
      (node (ref "SV4") (pin "1") (pinfunction "1_1") (pintype "passive"))
    )
    (net (code "44") (name "Net-(S37-P)") (class "Default")
      (node (ref "S37") (pin "2") (pinfunction "P_2") (pintype "passive"))
      (node (ref "S43") (pin "2") (pinfunction "P_2") (pintype "passive"))
      (node (ref "SV1") (pin "6") (pinfunction "6_6") (pintype "passive"))
    )
    (net (code "45") (name "Net-(S38-P)") (class "Default")
      (node (ref "S38") (pin "2") (pinfunction "P_2") (pintype "passive"))
      (node (ref "S44") (pin "2") (pinfunction "P_2") (pintype "passive"))
      (node (ref "SV1") (pin "5") (pinfunction "5_5") (pintype "passive"))
    )
    (net (code "46") (name "Net-(S39-P)") (class "Default")
      (node (ref "S39") (pin "2") (pinfunction "P_2") (pintype "passive"))
      (node (ref "S45") (pin "2") (pinfunction "P_2") (pintype "passive"))
      (node (ref "SV1") (pin "4") (pinfunction "4_4") (pintype "passive"))
    )
    (net (code "47") (name "Net-(S40-P)") (class "Default")
      (node (ref "S40") (pin "2") (pinfunction "P_2") (pintype "passive"))
      (node (ref "S46") (pin "2") (pinfunction "P_2") (pintype "passive"))
      (node (ref "SV1") (pin "3") (pinfunction "3_3") (pintype "passive"))
    )
    (net (code "48") (name "Net-(S41-P)") (class "Default")
      (node (ref "S41") (pin "2") (pinfunction "P_2") (pintype "passive"))
      (node (ref "S47") (pin "2") (pinfunction "P_2") (pintype "passive"))
      (node (ref "SV1") (pin "2") (pinfunction "2_2") (pintype "passive"))
    )
    (net (code "49") (name "Net-(S42-P)") (class "Default")
      (node (ref "S42") (pin "2") (pinfunction "P_2") (pintype "passive"))
      (node (ref "S48") (pin "2") (pinfunction "P_2") (pintype "passive"))
      (node (ref "SV1") (pin "1") (pinfunction "1_1") (pintype "passive"))
    )
    (net (code "50") (name "unconnected-(J1-1-PadP$1)") (class "Default")
      (node (ref "J1") (pin "P$1") (pinfunction "1_P$1") (pintype "passive"))
    )
    (net (code "51") (name "unconnected-(X25-Pad1)") (class "Default")
      (node (ref "X25") (pin "1") (pinfunction "1_1") (pintype "passive"))
    )
  )
)
